# can.net
KiCad netlist of a schematic drawn in Altium Designer
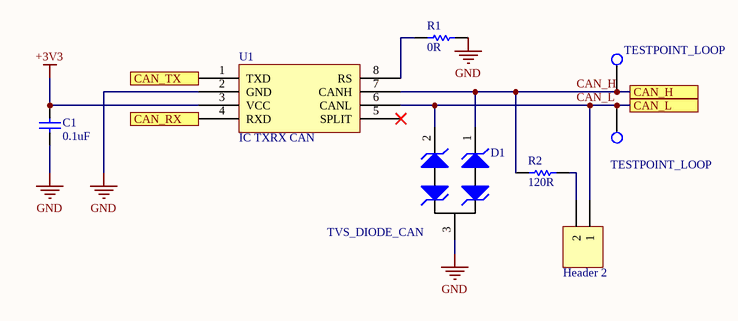
[diagram p0: can.SchDoc]

(export (version "E")
  (design (tool "Eeschema 10.0.6"))
  (components
    (comp (ref "1")
      (value "Header 2")
      (footprint "HDR1X2")
      (description "Header, 2-Pin")
      (fields (field (name "PUBLISHER") "Altium Limited"))
      (libsource (lib "Miscellaneous Connectors") (part "Header 2"))
    )
    (comp (ref "C1")
      (value "0.1uF")
      (footprint "CAPC0603(1608)55_N")
      (description "CAP CER 0.1UF 16V X7R 0603")
      (fields (field (name "MANUFACTURER") "Yageo") (field (name "MPN") "CC0603KRX7R7BB104"))
      (libsource (lib "UWRT_Schematic_Library_2019") (part "CAP_0.1uF_16V_0603"))
    )
    (comp (ref "CANH1")
      (value "TESTPOINT_LOOP")
      (footprint "TESTPOINT_LOOP")
      (libsource (lib "UWRT_Schematic_Library_2019") (part "TESTPOINT_LOOP"))
    )
    (comp (ref "CANL1")
      (value "TESTPOINT_LOOP")
      (footprint "TESTPOINT_LOOP")
      (libsource (lib "UWRT_Schematic_Library_2019") (part "TESTPOINT_LOOP"))
    )
    (comp (ref "D1")
      (value "TVS_DIODE_CAN")
      (footprint "NXP-SOT323-3")
      (description "TVS DIODE 24V 41V SOT323-3")
      (fields (field (name "MANUFACTURER") "Nexperia USA Inc.") (field (name "MPN") "PESD2CAN,215"))
      (libsource (lib "UWRT_Schematic_Library_2019") (part "TVS_DIODE_CAN"))
    )
    (comp (ref "R1")
      (value "0R")
      (footprint "RESC0603(1608)_N")
      (description "RES SMD 0 OHM JUMPER 1/10W 0603")
      (fields (field (name "MANUFACTURER") "Yageo") (field (name "MPN") "RC0603JR-070RL"))
      (libsource (lib "UWRT_Schematic_Library_2019") (part "RES_0R_0603"))
    )
    (comp (ref "R2")
      (value "120R")
      (footprint "RESC0603(1608)_N")
      (description "RES SMD 120 OHM 5% 1/10W 0603")
      (fields (field (name "MANUFACTURER") "Yageo") (field (name "TOLERANCE") "5%"))
      (libsource (lib "UWRT_Schematic_Library_2019") (part "RES_120R_0603"))
    )
    (comp (ref "U1")
      (value "IC TXRX CAN")
      (footprint "LT-S8_N")
      (description "IC TXRX CAN 4MBPS 8SO")
      (fields (field (name "MANUFACTURER") "Linear Technologies") (field (name "MPN") "LTC2875IS8#PBF"))
      (libsource (lib "UWRT_Schematic_Library_2019") (part "LTC2875"))
    )
  )
  (nets
    (net (code "1") (name "+3V3") (class "Default")
      (node (ref "C1") (pin "2") (pinfunction "2_2") (pintype "passive"))
      (node (ref "U1") (pin "3") (pinfunction "VCC_3") (pintype "passive"))
    )
    (net (code "2") (name "/CAN_H") (class "Default")
      (node (ref "CANH1") (pin "1") (pinfunction "=value_1") (pintype "passive"))
      (node (ref "D1") (pin "1") (pinfunction "1_1") (pintype "passive"))
      (node (ref "R2") (pin "1") (pinfunction "1_1") (pintype "passive"))
      (node (ref "U1") (pin "7") (pinfunction "CANH_7") (pintype "passive"))
    )
    (net (code "3") (name "/CAN_L") (class "Default")
      (node (ref "1") (pin "1") (pinfunction "1_1") (pintype "passive"))
      (node (ref "CANL1") (pin "1") (pinfunction "=value_1") (pintype "passive"))
      (node (ref "D1") (pin "2") (pinfunction "2_2") (pintype "passive"))
      (node (ref "U1") (pin "6") (pinfunction "CANL_6") (pintype "passive"))
    )
    (net (code "4") (name "/CAN_RX") (class "Default")
      (node (ref "U1") (pin "4") (pinfunction "RXD_4") (pintype "passive"))
    )
    (net (code "5") (name "/CAN_TX") (class "Default")
      (node (ref "U1") (pin "1") (pinfunction "TXD_1") (pintype "passive"))
    )
    (net (code "6") (name "GND") (class "Default")
      (node (ref "C1") (pin "1") (pinfunction "1_1") (pintype "passive"))
      (node (ref "D1") (pin "3") (pinfunction "3_3") (pintype "passive"))
      (node (ref "R1") (pin "2") (pinfunction "2_2") (pintype "passive"))
      (node (ref "U1") (pin "2") (pinfunction "GND_2") (pintype "passive"))
    )
    (net (code "7") (name "Net-(1-Pad2)") (class "Default")
      (node (ref "1") (pin "2") (pinfunction "2_2") (pintype "passive"))
      (node (ref "R2") (pin "2") (pinfunction "2_2") (pintype "passive"))
    )
    (net (code "8") (name "Net-(U1-RS)") (class "Default")
      (node (ref "R1") (pin "1") (pinfunction "1_1") (pintype "passive"))
      (node (ref "U1") (pin "8") (pinfunction "RS_8") (pintype "passive"))
    )
    (net (code "9") (name "unconnected-(U1-SPLIT-Pad5)") (class "Default")
      (node (ref "U1") (pin "5") (pinfunction "SPLIT_5") (pintype "passive+no_connect"))
    )
  )
)
